# Rocket-Switch-Interface_1_01.net
KiCad netlist of a schematic drawn in EAGLE
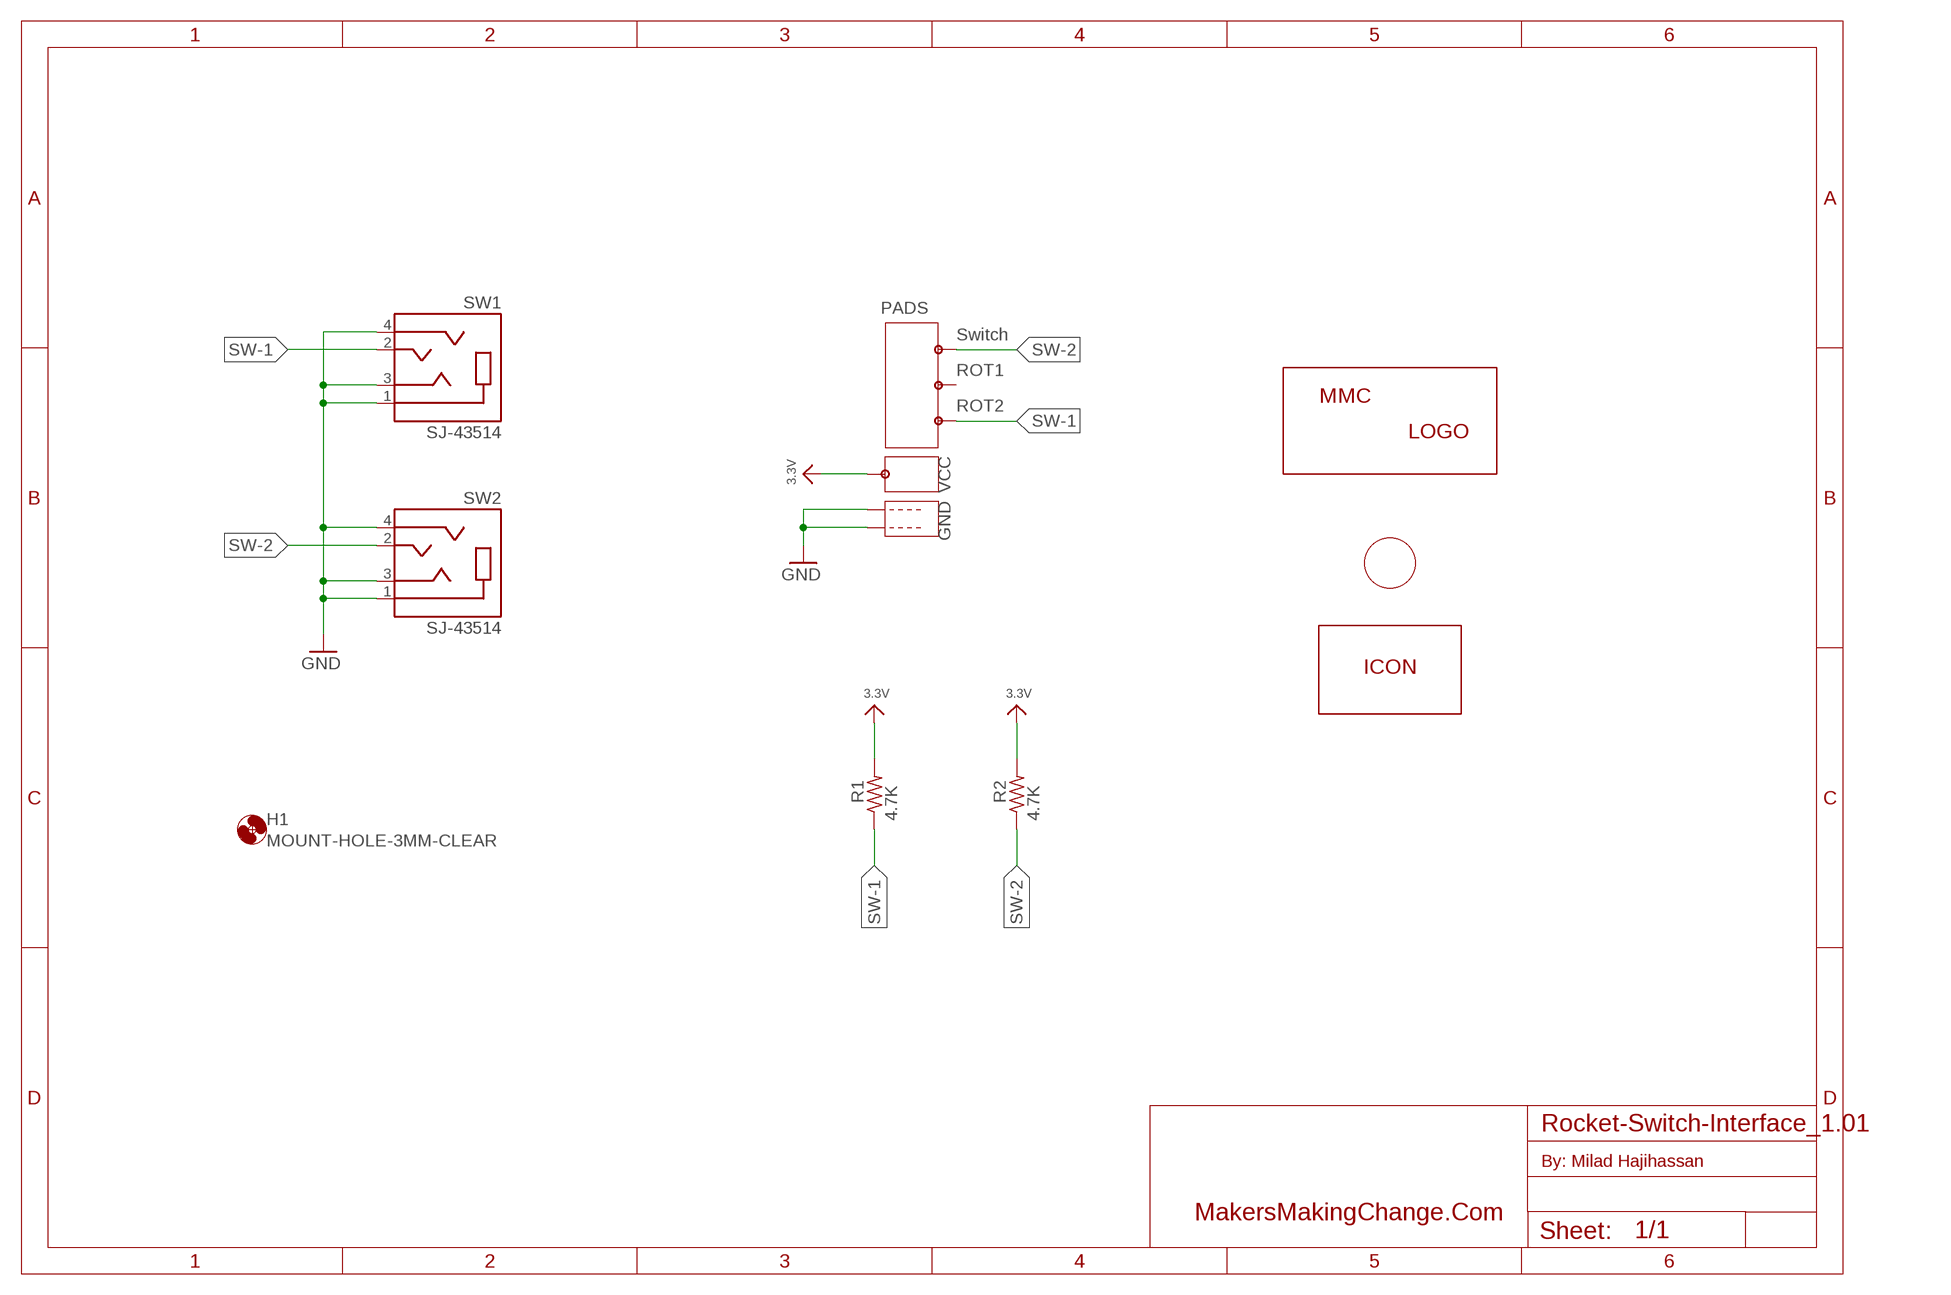
[diagram p0: schematic, sheet 1]

(export (version "E")
  (design (tool "Eeschema 10.0.6"))
  (components
    (comp (ref "H1")
      (value "MOUNT-HOLE-3MM-CLEAR")
      (footprint "eagle-import:HOLE-3MM-CLEAR")
      (libsource (lib "eagle-import") (part "MOUNT-HOLE-3MM-CLEAR"))
    )
    (comp (ref "LABEL_BACKGROUND")
      (value "MMC_ICON-ROCKET-SW")
      (footprint "eagle-import:ICON_ROCKET-SWITCH")
      (libsource (lib "eagle-import") (part "MMC_ICON-ROCKET-SW"))
    )
    (comp (ref "LABEL_DEVICE")
      (value "MMC_LABEL-ROCKET-SW")
      (footprint "eagle-import:LABEL-ROCKET-SWITCH")
      (libsource (lib "eagle-import") (part "MMC_LABEL-ROCKET-SW"))
    )
    (comp (ref "LABEL_LOGO")
      (value "MMC_LOGO-XSM")
      (footprint "eagle-import:MMC_X-SMALL_LOGO")
      (libsource (lib "eagle-import") (part "MMC_LOGO-XSM"))
    )
    (comp (ref "PADS")
      (value "PADS-ROTARY-TRINKEY-2")
      (footprint "eagle-import:PADS-ROTARY-TRINKEY-2")
      (libsource (lib "eagle-import") (part "PADS-ROTARY-TRINKEY-2"))
    )
    (comp (ref "R1")
      (value "4.7K")
      (footprint "eagle-import:RESISTOR_0204_5")
      (libsource (lib "eagle-import") (part "RESISTOR-US-0204/5"))
    )
    (comp (ref "R2")
      (value "4.7K")
      (footprint "eagle-import:RESISTOR_0204_5")
      (libsource (lib "eagle-import") (part "RESISTOR-US-0204/5"))
    )
    (comp (ref "SW1")
      (value "SJ-43514")
      (footprint "eagle-import:CUI_SJ-43514")
      (libsource (lib "eagle-import") (part "SJ-43514"))
    )
    (comp (ref "SW2")
      (value "SJ-43514")
      (footprint "eagle-import:CUI_SJ-43514")
      (libsource (lib "eagle-import") (part "SJ-43514"))
    )
  )
  (nets
    (net (code "1") (name "3.3V") (class "Default")
      (node (ref "PADS") (pin "P$VCC") (pinfunction "P$VCC_P$VCC") (pintype "passive"))
      (node (ref "R1") (pin "2") (pinfunction "2_2") (pintype "passive"))
      (node (ref "R2") (pin "2") (pinfunction "2_2") (pintype "passive"))
    )
    (net (code "2") (name "GND") (class "Default")
      (node (ref "PADS") (pin "P$GND1") (pinfunction "P$GND1_P$GND1") (pintype "passive"))
      (node (ref "PADS") (pin "P$GND2") (pinfunction "P$GND2_P$GND2") (pintype "passive"))
      (node (ref "SW1") (pin "1") (pinfunction "SLEEVE_1") (pintype "passive"))
      (node (ref "SW1") (pin "3") (pinfunction "RING1_3") (pintype "passive"))
      (node (ref "SW1") (pin "4") (pinfunction "RING2_4") (pintype "passive"))
      (node (ref "SW2") (pin "1") (pinfunction "SLEEVE_1") (pintype "passive"))
      (node (ref "SW2") (pin "3") (pinfunction "RING1_3") (pintype "passive"))
      (node (ref "SW2") (pin "4") (pinfunction "RING2_4") (pintype "passive"))
    )
    (net (code "3") (name "SW-1") (class "Default")
      (node (ref "PADS") (pin "P$ROT2") (pinfunction "P$ROT2_P$ROT2") (pintype "passive"))
      (node (ref "R1") (pin "1") (pinfunction "1_1") (pintype "passive"))
      (node (ref "SW1") (pin "2") (pinfunction "TIP_2") (pintype "passive"))
    )
    (net (code "4") (name "SW-2") (class "Default")
      (node (ref "PADS") (pin "P$SW") (pinfunction "P$SW_P$SW") (pintype "passive"))
      (node (ref "R2") (pin "1") (pinfunction "1_1") (pintype "passive"))
      (node (ref "SW2") (pin "2") (pinfunction "TIP_2") (pintype "passive"))
    )
    (net (code "5") (name "unconnected-(PADS-PadP$ROT1)") (class "Default")
      (node (ref "PADS") (pin "P$ROT1") (pinfunction "P$ROT1_P$ROT1") (pintype "passive"))
    )
  )
)
